# attinier85-batty-shield-mk-2_4.net
KiCad netlist of a schematic drawn in EAGLE
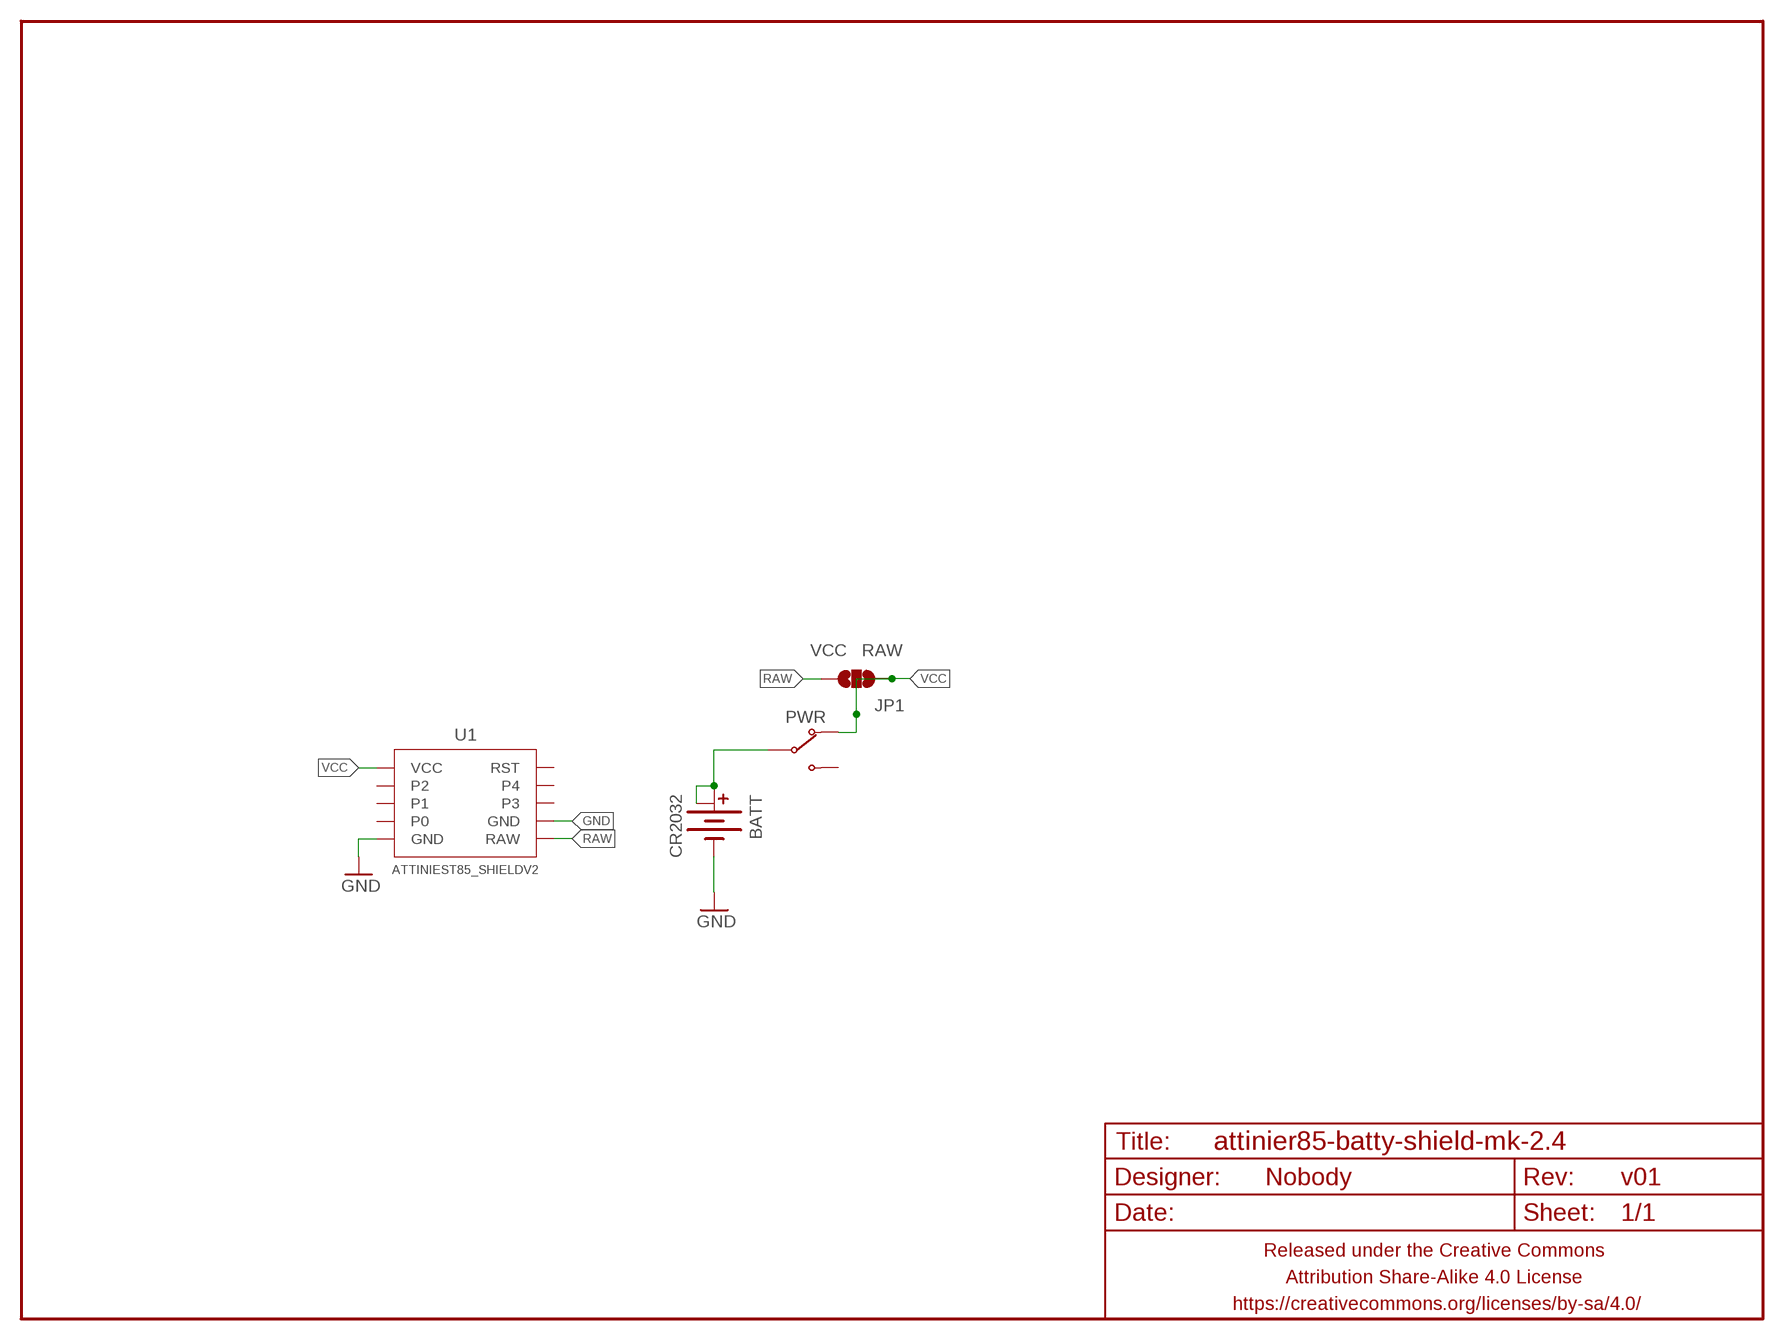
[diagram p0: schematic, sheet 1]

(export (version "E")
  (design (tool "Eeschema 10.0.6"))
  (components
    (comp (ref "BATT")
      (value "CR2032")
      (footprint "eagle-import:BATTCON_20MM_MINE")
      (libsource (lib "eagle-import") (part "BATTERY-COINCR2032_SMD"))
    )
    (comp (ref "FRAME1")
      (value "FRAME-LETTERNO_PACKAGE")
      (footprint "eagle-import:DUMMY")
      (fields (field (name "DESIGNER") "Nobody"))
      (libsource (lib "eagle-import") (part "FRAME-LETTERNO_PACKAGE"))
    )
    (comp (ref "JP1")
      (value "VCC RAW")
      (footprint "eagle-import:PAD-JUMPER-3-NO_YES_SILK_FULL_BOX")
      (libsource (lib "eagle-import") (part "JUMPER-PAD-3-NOFULL_BOX_SILK"))
    )
    (comp (ref "PWR")
      (value "SWITCH-SPDTPTH-RA-2MM")
      (footprint "eagle-import:SPDT-RA-2MM")
      (libsource (lib "eagle-import") (part "SWITCH-SPDTPTH-RA-2MM"))
    )
    (comp (ref "U1")
      (value "ATTINIEST85_SHIELDV2")
      (footprint "eagle-import:ATTINIEST85_SHIELD_V2")
      (libsource (lib "eagle-import") (part "ATTINIEST85_SHIELDV2"))
    )
  )
  (nets
    (net (code "1") (name "GND") (class "Default")
      (node (ref "BATT") (pin "BOTTOM") (pinfunction "-_BOTTOM") (pintype "bidirectional"))
      (node (ref "U1") (pin "GND@1") (pinfunction "GND_GND@1") (pintype "bidirectional"))
      (node (ref "U1") (pin "GND@2") (pinfunction "GND_GND@2") (pintype "bidirectional"))
    )
    (net (code "2") (name "Net-(BATT-+)") (class "Default")
      (node (ref "BATT") (pin "TOP@1") (pinfunction "+_TOP@1") (pintype "bidirectional"))
      (node (ref "BATT") (pin "TOP@2") (pinfunction "+1_TOP@2") (pintype "bidirectional"))
      (node (ref "PWR") (pin "2") (pinfunction "COM_2") (pintype "passive"))
    )
    (net (code "3") (name "RAW") (class "Default")
      (node (ref "JP1") (pin "1") (pinfunction "1_1") (pintype "passive"))
      (node (ref "U1") (pin "RAW") (pinfunction "RAW_RAW") (pintype "bidirectional"))
    )
    (net (code "4") (name "VCC") (class "Default")
      (node (ref "JP1") (pin "2") (pinfunction "2_2") (pintype "passive"))
      (node (ref "JP1") (pin "3") (pinfunction "3_3") (pintype "passive"))
      (node (ref "PWR") (pin "1") (pinfunction "NC_1") (pintype "passive"))
      (node (ref "U1") (pin "VCC") (pinfunction "VCC_VCC") (pintype "bidirectional"))
    )
    (net (code "5") (name "unconnected-(PWR-NO-Pad3)") (class "Default")
      (node (ref "PWR") (pin "3") (pinfunction "NO_3") (pintype "passive"))
    )
    (net (code "6") (name "unconnected-(U1-P0-Pad0)") (class "Default")
      (node (ref "U1") (pin "0") (pinfunction "P0_0") (pintype "bidirectional"))
    )
    (net (code "7") (name "unconnected-(U1-P1-Pad1)") (class "Default")
      (node (ref "U1") (pin "1") (pinfunction "P1_1") (pintype "bidirectional"))
    )
    (net (code "8") (name "unconnected-(U1-P2-Pad2)") (class "Default")
      (node (ref "U1") (pin "2") (pinfunction "P2_2") (pintype "bidirectional"))
    )
    (net (code "9") (name "unconnected-(U1-P3-Pad3)") (class "Default")
      (node (ref "U1") (pin "3") (pinfunction "P3_3") (pintype "bidirectional"))
    )
    (net (code "10") (name "unconnected-(U1-P4-Pad4)") (class "Default")
      (node (ref "U1") (pin "4") (pinfunction "P4_4") (pintype "bidirectional"))
    )
    (net (code "11") (name "unconnected-(U1-PadRST)") (class "Default")
      (node (ref "U1") (pin "RST") (pinfunction "RST_RST") (pintype "bidirectional"))
    )
  )
)
